# MURMERDUINO_CAM_MOUNTER.net
KiCad netlist of a schematic drawn in EAGLE
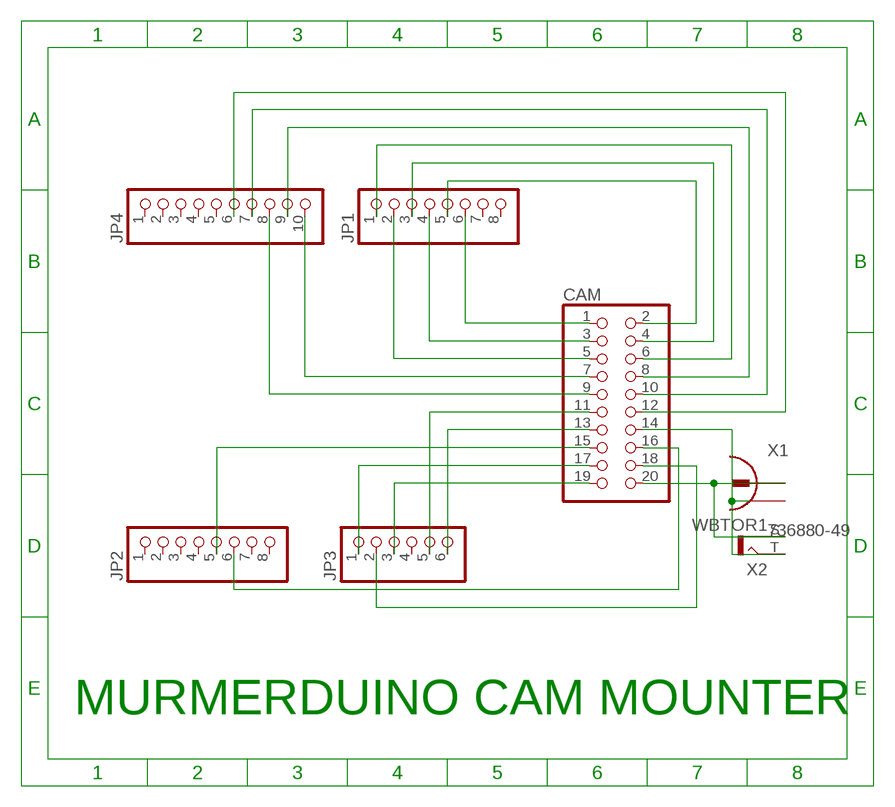
[diagram p0: schematic, sheet 1]

(export (version "E")
  (design (tool "Eeschema 10.0.6"))
  (components
    (comp (ref "CAM")
      (value "PINHD-2X10")
      (footprint "eagle-import:2X10")
      (libsource (lib "eagle-import") (part "PINHD-2X10"))
    )
    (comp (ref "JP1")
      (value "PINHD-1X8")
      (footprint "eagle-import:1X08")
      (libsource (lib "eagle-import") (part "PINHD-1X8"))
    )
    (comp (ref "JP2")
      (value "PINHD-1X8")
      (footprint "eagle-import:1X08")
      (libsource (lib "eagle-import") (part "PINHD-1X8"))
    )
    (comp (ref "JP3")
      (value "PINHD-1X6")
      (footprint "eagle-import:1X06")
      (libsource (lib "eagle-import") (part "PINHD-1X6"))
    )
    (comp (ref "JP4")
      (value "PINHD-1X10")
      (footprint "eagle-import:1X10")
      (libsource (lib "eagle-import") (part "PINHD-1X10"))
    )
    (comp (ref "X1")
      (value "736880-49")
      (footprint "eagle-import:736880-49")
      (libsource (lib "eagle-import") (part "736880-49"))
    )
    (comp (ref "X2")
      (value "WBTOR1")
      (footprint "eagle-import:WBTOR1")
      (fields (field (name "MPN") "WBTOR 1 BLACK"))
      (libsource (lib "eagle-import") (part "WBTOR1"))
    )
  )
  (nets
    (net (code "1") (name "Net-(CAM-Pad1)") (class "Default")
      (node (ref "CAM") (pin "1") (pinfunction "1_1") (pintype "passive"))
      (node (ref "JP1") (pin "6") (pinfunction "6_6") (pintype "passive"))
    )
    (net (code "2") (name "Net-(CAM-Pad2)") (class "Default")
      (node (ref "CAM") (pin "2") (pinfunction "2_2") (pintype "passive"))
      (node (ref "JP1") (pin "5") (pinfunction "5_5") (pintype "passive"))
    )
    (net (code "3") (name "Net-(CAM-Pad3)") (class "Default")
      (node (ref "CAM") (pin "3") (pinfunction "3_3") (pintype "passive"))
      (node (ref "JP1") (pin "4") (pinfunction "4_4") (pintype "passive"))
    )
    (net (code "4") (name "Net-(CAM-Pad4)") (class "Default")
      (node (ref "CAM") (pin "4") (pinfunction "4_4") (pintype "passive"))
      (node (ref "JP1") (pin "3") (pinfunction "3_3") (pintype "passive"))
    )
    (net (code "5") (name "Net-(CAM-Pad5)") (class "Default")
      (node (ref "CAM") (pin "5") (pinfunction "5_5") (pintype "passive"))
      (node (ref "JP1") (pin "2") (pinfunction "2_2") (pintype "passive"))
    )
    (net (code "6") (name "Net-(CAM-Pad6)") (class "Default")
      (node (ref "CAM") (pin "6") (pinfunction "6_6") (pintype "passive"))
      (node (ref "JP1") (pin "1") (pinfunction "1_1") (pintype "passive"))
    )
    (net (code "7") (name "Net-(CAM-Pad7)") (class "Default")
      (node (ref "CAM") (pin "7") (pinfunction "7_7") (pintype "passive"))
      (node (ref "JP4") (pin "10") (pinfunction "10_10") (pintype "passive"))
    )
    (net (code "8") (name "Net-(CAM-Pad8)") (class "Default")
      (node (ref "CAM") (pin "8") (pinfunction "8_8") (pintype "passive"))
      (node (ref "JP4") (pin "9") (pinfunction "9_9") (pintype "passive"))
    )
    (net (code "9") (name "Net-(CAM-Pad9)") (class "Default")
      (node (ref "CAM") (pin "9") (pinfunction "9_9") (pintype "passive"))
      (node (ref "JP4") (pin "8") (pinfunction "8_8") (pintype "passive"))
    )
    (net (code "10") (name "Net-(CAM-Pad10)") (class "Default")
      (node (ref "CAM") (pin "10") (pinfunction "10_10") (pintype "passive"))
      (node (ref "JP4") (pin "7") (pinfunction "7_7") (pintype "passive"))
    )
    (net (code "11") (name "Net-(CAM-Pad11)") (class "Default")
      (node (ref "CAM") (pin "11") (pinfunction "11_11") (pintype "passive"))
      (node (ref "JP3") (pin "5") (pinfunction "5_5") (pintype "passive"))
    )
    (net (code "12") (name "Net-(CAM-Pad12)") (class "Default")
      (node (ref "CAM") (pin "12") (pinfunction "12_12") (pintype "passive"))
      (node (ref "JP4") (pin "6") (pinfunction "6_6") (pintype "passive"))
    )
    (net (code "13") (name "Net-(CAM-Pad13)") (class "Default")
      (node (ref "CAM") (pin "13") (pinfunction "13_13") (pintype "passive"))
      (node (ref "JP3") (pin "6") (pinfunction "6_6") (pintype "passive"))
    )
    (net (code "14") (name "Net-(CAM-Pad14)") (class "Default")
      (node (ref "CAM") (pin "14") (pinfunction "14_14") (pintype "passive"))
      (node (ref "X2") (pin "T") (pinfunction "T_T") (pintype "passive"))
    )
    (net (code "15") (name "Net-(CAM-Pad15)") (class "Default")
      (node (ref "CAM") (pin "15") (pinfunction "15_15") (pintype "passive"))
      (node (ref "JP2") (pin "5") (pinfunction "5_5") (pintype "passive"))
    )
    (net (code "16") (name "Net-(CAM-Pad16)") (class "Default")
      (node (ref "CAM") (pin "16") (pinfunction "16_16") (pintype "passive"))
      (node (ref "JP2") (pin "6") (pinfunction "6_6") (pintype "passive"))
    )
    (net (code "17") (name "Net-(CAM-Pad17)") (class "Default")
      (node (ref "CAM") (pin "17") (pinfunction "17_17") (pintype "passive"))
      (node (ref "JP3") (pin "1") (pinfunction "1_1") (pintype "passive"))
    )
    (net (code "18") (name "Net-(CAM-Pad18)") (class "Default")
      (node (ref "CAM") (pin "18") (pinfunction "18_18") (pintype "passive"))
      (node (ref "JP3") (pin "2") (pinfunction "2_2") (pintype "passive"))
    )
    (net (code "19") (name "Net-(CAM-Pad19)") (class "Default")
      (node (ref "CAM") (pin "19") (pinfunction "19_19") (pintype "passive"))
      (node (ref "JP3") (pin "3") (pinfunction "3_3") (pintype "passive"))
    )
    (net (code "20") (name "Net-(CAM-Pad20)") (class "Default")
      (node (ref "CAM") (pin "20") (pinfunction "20_20") (pintype "passive"))
      (node (ref "X1") (pin "1") (pinfunction "1_1") (pintype "passive"))
      (node (ref "X2") (pin "S") (pinfunction "S_S") (pintype "passive"))
    )
    (net (code "21") (name "unconnected-(JP1-Pad7)") (class "Default")
      (node (ref "JP1") (pin "7") (pinfunction "7_7") (pintype "passive"))
    )
    (net (code "22") (name "unconnected-(JP1-Pad8)") (class "Default")
      (node (ref "JP1") (pin "8") (pinfunction "8_8") (pintype "passive"))
    )
    (net (code "23") (name "unconnected-(JP2-Pad1)") (class "Default")
      (node (ref "JP2") (pin "1") (pinfunction "1_1") (pintype "passive"))
    )
    (net (code "24") (name "unconnected-(JP2-Pad2)") (class "Default")
      (node (ref "JP2") (pin "2") (pinfunction "2_2") (pintype "passive"))
    )
    (net (code "25") (name "unconnected-(JP2-Pad3)") (class "Default")
      (node (ref "JP2") (pin "3") (pinfunction "3_3") (pintype "passive"))
    )
    (net (code "26") (name "unconnected-(JP2-Pad4)") (class "Default")
      (node (ref "JP2") (pin "4") (pinfunction "4_4") (pintype "passive"))
    )
    (net (code "27") (name "unconnected-(JP2-Pad7)") (class "Default")
      (node (ref "JP2") (pin "7") (pinfunction "7_7") (pintype "passive"))
    )
    (net (code "28") (name "unconnected-(JP2-Pad8)") (class "Default")
      (node (ref "JP2") (pin "8") (pinfunction "8_8") (pintype "passive"))
    )
    (net (code "29") (name "unconnected-(JP3-Pad4)") (class "Default")
      (node (ref "JP3") (pin "4") (pinfunction "4_4") (pintype "passive"))
    )
    (net (code "30") (name "unconnected-(JP4-Pad1)") (class "Default")
      (node (ref "JP4") (pin "1") (pinfunction "1_1") (pintype "passive"))
    )
    (net (code "31") (name "unconnected-(JP4-Pad2)") (class "Default")
      (node (ref "JP4") (pin "2") (pinfunction "2_2") (pintype "passive"))
    )
    (net (code "32") (name "unconnected-(JP4-Pad3)") (class "Default")
      (node (ref "JP4") (pin "3") (pinfunction "3_3") (pintype "passive"))
    )
    (net (code "33") (name "unconnected-(JP4-Pad4)") (class "Default")
      (node (ref "JP4") (pin "4") (pinfunction "4_4") (pintype "passive"))
    )
    (net (code "34") (name "unconnected-(JP4-Pad5)") (class "Default")
      (node (ref "JP4") (pin "5") (pinfunction "5_5") (pintype "passive"))
    )
    (net (code "35") (name "unconnected-(X1-2-Pad2@2)") (class "Default")
      (node (ref "X1") (pin "2@2") (pinfunction "2_2@2") (pintype "passive"))
    )
    (net (code "36") (name "unconnected-(X1-Pad2)") (class "Default")
      (node (ref "X1") (pin "2") (pinfunction "2_2") (pintype "passive"))
    )
  )
)
